# MPR121-Breakout-v13.net
KiCad netlist of a schematic drawn in EAGLE
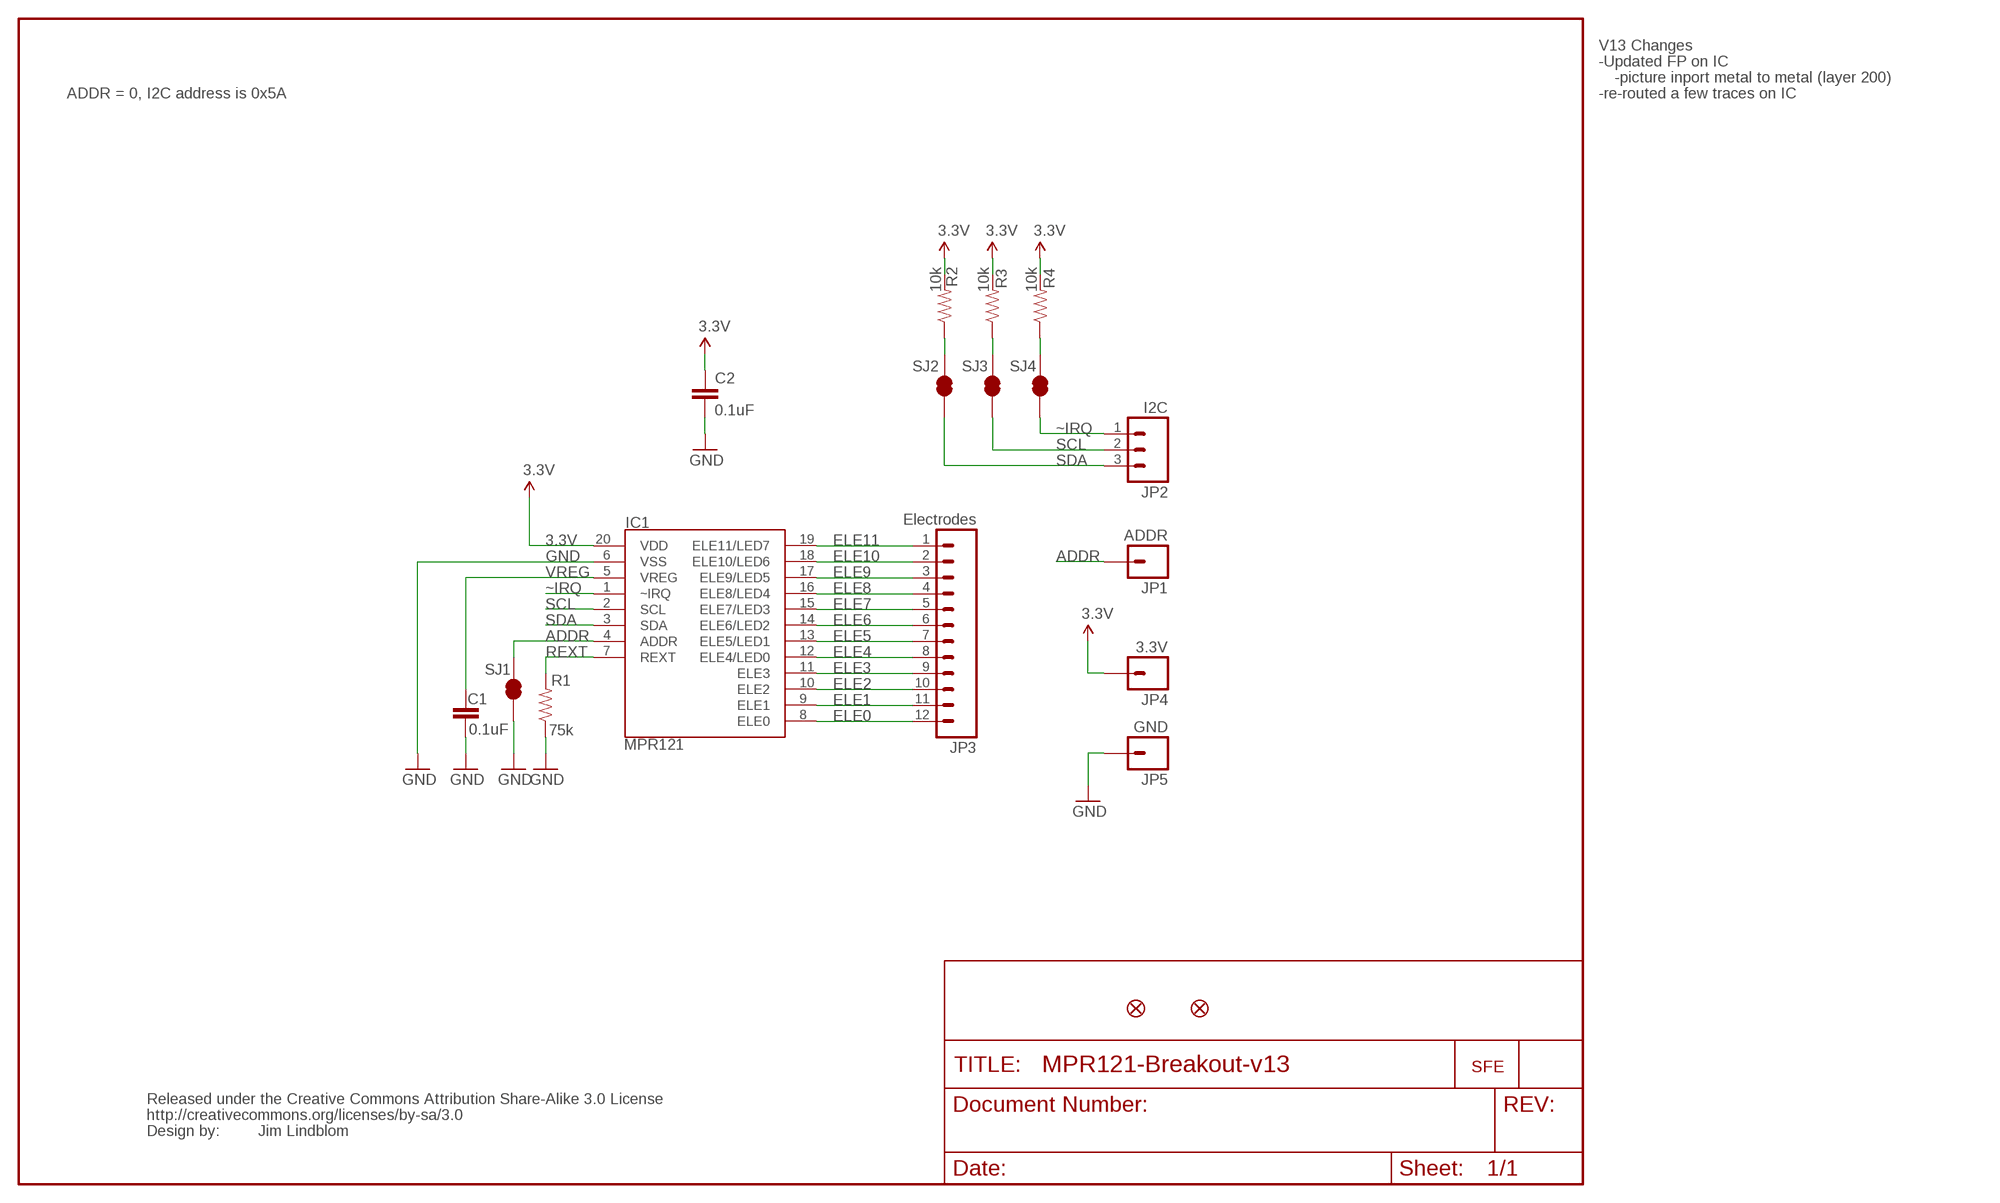
[diagram p0: schematic, sheet 1]

(export (version "E")
  (design (tool "Eeschema 10.0.6"))
  (components
    (comp (ref "C1")
      (value "0.1uF")
      (footprint "eagle-import:0603-CAP")
      (libsource (lib "eagle-import") (part "CAP0603-CAP"))
    )
    (comp (ref "C2")
      (value "0.1uF")
      (footprint "eagle-import:0603-CAP")
      (libsource (lib "eagle-import") (part "CAP0603-CAP"))
    )
    (comp (ref "IC1")
      (value "MPR121")
      (footprint "eagle-import:QFN-20-0.4MM-V2")
      (libsource (lib "eagle-import") (part "MPR121V2"))
    )
    (comp (ref "JP1")
      (value "ADDR")
      (footprint "eagle-import:1X01")
      (libsource (lib "eagle-import") (part "M01PTH"))
    )
    (comp (ref "JP2")
      (value "I2C")
      (footprint "eagle-import:1X03")
      (libsource (lib "eagle-import") (part "M03PTH"))
    )
    (comp (ref "JP3")
      (value "Electrodes")
      (footprint "eagle-import:1X12")
      (libsource (lib "eagle-import") (part "M12PTH"))
    )
    (comp (ref "JP4")
      (value "3.3V")
      (footprint "eagle-import:1X01")
      (libsource (lib "eagle-import") (part "M01PTH"))
    )
    (comp (ref "JP5")
      (value "GND")
      (footprint "eagle-import:1X01")
      (libsource (lib "eagle-import") (part "M01PTH"))
    )
    (comp (ref "JP7")
      (value "LOGO-SFENEW")
      (footprint "eagle-import:SFE-NEW-WEBLOGO")
      (libsource (lib "eagle-import") (part "LOGO-SFENEW"))
    )
    (comp (ref "JP8")
      (value "FIDUCIAL1X2")
      (footprint "eagle-import:FIDUCIAL-1X2")
      (libsource (lib "eagle-import") (part "FIDUCIAL1X2"))
    )
    (comp (ref "JP9")
      (value "FIDUCIAL1X2")
      (footprint "eagle-import:FIDUCIAL-1X2")
      (libsource (lib "eagle-import") (part "FIDUCIAL1X2"))
    )
    (comp (ref "R1")
      (value "75k")
      (footprint "eagle-import:0603-RES")
      (libsource (lib "eagle-import") (part "RESISTOR0603-RES"))
    )
    (comp (ref "R2")
      (value "10k")
      (footprint "eagle-import:0603-RES")
      (libsource (lib "eagle-import") (part "RESISTOR0603-RES"))
    )
    (comp (ref "R3")
      (value "10k")
      (footprint "eagle-import:0603-RES")
      (libsource (lib "eagle-import") (part "RESISTOR0603-RES"))
    )
    (comp (ref "R4")
      (value "10k")
      (footprint "eagle-import:0603-RES")
      (libsource (lib "eagle-import") (part "RESISTOR0603-RES"))
    )
    (comp (ref "SJ1")
      (value "SOLDERJUMPERTRACE")
      (footprint "eagle-import:SJ_2S-TRACE")
      (libsource (lib "eagle-import") (part "SOLDERJUMPERTRACE"))
    )
    (comp (ref "SJ2")
      (value "SOLDERJUMPERTRACE")
      (footprint "eagle-import:SJ_2S-TRACE")
      (libsource (lib "eagle-import") (part "SOLDERJUMPERTRACE"))
    )
    (comp (ref "SJ3")
      (value "SOLDERJUMPERTRACE")
      (footprint "eagle-import:SJ_2S-TRACE")
      (libsource (lib "eagle-import") (part "SOLDERJUMPERTRACE"))
    )
    (comp (ref "SJ4")
      (value "SOLDERJUMPERTRACE")
      (footprint "eagle-import:SJ_2S-TRACE")
      (libsource (lib "eagle-import") (part "SOLDERJUMPERTRACE"))
    )
    (comp (ref "U$1")
      (value "CREATIVE_COMMONS")
      (footprint "eagle-import:CREATIVE_COMMONS")
      (libsource (lib "eagle-import") (part "CREATIVE_COMMONS"))
    )
  )
  (nets
    (net (code "1") (name "/ADDR") (class "Default")
      (node (ref "IC1") (pin "4") (pinfunction "ADDR_4") (pintype "bidirectional"))
      (node (ref "JP1") (pin "1") (pinfunction "1_1") (pintype "passive"))
      (node (ref "SJ1") (pin "2") (pinfunction "2_2") (pintype "passive"))
    )
    (net (code "2") (name "/ELE0") (class "Default")
      (node (ref "IC1") (pin "8") (pinfunction "ELE0_8") (pintype "bidirectional"))
      (node (ref "JP3") (pin "12") (pinfunction "12_12") (pintype "passive"))
    )
    (net (code "3") (name "/ELE1") (class "Default")
      (node (ref "IC1") (pin "9") (pinfunction "ELE1_9") (pintype "bidirectional"))
      (node (ref "JP3") (pin "11") (pinfunction "11_11") (pintype "passive"))
    )
    (net (code "4") (name "/ELE2") (class "Default")
      (node (ref "IC1") (pin "10") (pinfunction "ELE2_10") (pintype "bidirectional"))
      (node (ref "JP3") (pin "10") (pinfunction "10_10") (pintype "passive"))
    )
    (net (code "5") (name "/ELE3") (class "Default")
      (node (ref "IC1") (pin "11") (pinfunction "ELE3_11") (pintype "bidirectional"))
      (node (ref "JP3") (pin "9") (pinfunction "9_9") (pintype "passive"))
    )
    (net (code "6") (name "/ELE4") (class "Default")
      (node (ref "IC1") (pin "12") (pinfunction "ELE4/LED0_12") (pintype "bidirectional"))
      (node (ref "JP3") (pin "8") (pinfunction "8_8") (pintype "passive"))
    )
    (net (code "7") (name "/ELE5") (class "Default")
      (node (ref "IC1") (pin "13") (pinfunction "ELE5/LED1_13") (pintype "bidirectional"))
      (node (ref "JP3") (pin "7") (pinfunction "7_7") (pintype "passive"))
    )
    (net (code "8") (name "/ELE6") (class "Default")
      (node (ref "IC1") (pin "14") (pinfunction "ELE6/LED2_14") (pintype "bidirectional"))
      (node (ref "JP3") (pin "6") (pinfunction "6_6") (pintype "passive"))
    )
    (net (code "9") (name "/ELE7") (class "Default")
      (node (ref "IC1") (pin "15") (pinfunction "ELE7/LED3_15") (pintype "bidirectional"))
      (node (ref "JP3") (pin "5") (pinfunction "5_5") (pintype "passive"))
    )
    (net (code "10") (name "/ELE8") (class "Default")
      (node (ref "IC1") (pin "16") (pinfunction "ELE8/LED4_16") (pintype "bidirectional"))
      (node (ref "JP3") (pin "4") (pinfunction "4_4") (pintype "passive"))
    )
    (net (code "11") (name "/ELE9") (class "Default")
      (node (ref "IC1") (pin "17") (pinfunction "ELE9/LED5_17") (pintype "bidirectional"))
      (node (ref "JP3") (pin "3") (pinfunction "3_3") (pintype "passive"))
    )
    (net (code "12") (name "/ELE10") (class "Default")
      (node (ref "IC1") (pin "18") (pinfunction "ELE10/LED6_18") (pintype "bidirectional"))
      (node (ref "JP3") (pin "2") (pinfunction "2_2") (pintype "passive"))
    )
    (net (code "13") (name "/ELE11") (class "Default")
      (node (ref "IC1") (pin "19") (pinfunction "ELE11/LED7_19") (pintype "bidirectional"))
      (node (ref "JP3") (pin "1") (pinfunction "1_1") (pintype "passive"))
    )
    (net (code "14") (name "/REXT") (class "Default")
      (node (ref "IC1") (pin "7") (pinfunction "REXT_7") (pintype "bidirectional"))
      (node (ref "R1") (pin "2") (pinfunction "2_2") (pintype "passive"))
    )
    (net (code "15") (name "/SCL") (class "Default")
      (node (ref "IC1") (pin "2") (pinfunction "SCL_2") (pintype "bidirectional"))
      (node (ref "JP2") (pin "2") (pinfunction "2_2") (pintype "passive"))
      (node (ref "SJ3") (pin "1") (pinfunction "1_1") (pintype "passive"))
    )
    (net (code "16") (name "/SDA") (class "Default")
      (node (ref "IC1") (pin "3") (pinfunction "SDA_3") (pintype "bidirectional"))
      (node (ref "JP2") (pin "3") (pinfunction "3_3") (pintype "passive"))
      (node (ref "SJ2") (pin "1") (pinfunction "1_1") (pintype "passive"))
    )
    (net (code "17") (name "/VREG") (class "Default")
      (node (ref "C1") (pin "1") (pinfunction "1_1") (pintype "passive"))
      (node (ref "IC1") (pin "5") (pinfunction "VREG_5") (pintype "bidirectional"))
    )
    (net (code "18") (name "/~{IRQ}") (class "Default")
      (node (ref "IC1") (pin "1") (pinfunction "~{IRQ}_1") (pintype "bidirectional"))
      (node (ref "JP2") (pin "1") (pinfunction "1_1") (pintype "passive"))
      (node (ref "SJ4") (pin "1") (pinfunction "1_1") (pintype "passive"))
    )
    (net (code "19") (name "3.3V") (class "Default")
      (node (ref "C2") (pin "1") (pinfunction "1_1") (pintype "passive"))
      (node (ref "IC1") (pin "20") (pinfunction "VDD_20") (pintype "bidirectional"))
      (node (ref "JP4") (pin "1") (pinfunction "1_1") (pintype "passive"))
      (node (ref "R2") (pin "2") (pinfunction "2_2") (pintype "passive"))
      (node (ref "R3") (pin "2") (pinfunction "2_2") (pintype "passive"))
      (node (ref "R4") (pin "2") (pinfunction "2_2") (pintype "passive"))
    )
    (net (code "20") (name "GND") (class "Default")
      (node (ref "C1") (pin "2") (pinfunction "2_2") (pintype "passive"))
      (node (ref "C2") (pin "2") (pinfunction "2_2") (pintype "passive"))
      (node (ref "IC1") (pin "6") (pinfunction "VSS_6") (pintype "bidirectional"))
      (node (ref "JP5") (pin "1") (pinfunction "1_1") (pintype "passive"))
      (node (ref "R1") (pin "1") (pinfunction "1_1") (pintype "passive"))
      (node (ref "SJ1") (pin "1") (pinfunction "1_1") (pintype "passive"))
    )
    (net (code "21") (name "Net-(R2-Pad1)") (class "Default")
      (node (ref "R2") (pin "1") (pinfunction "1_1") (pintype "passive"))
      (node (ref "SJ2") (pin "2") (pinfunction "2_2") (pintype "passive"))
    )
    (net (code "22") (name "Net-(R3-Pad1)") (class "Default")
      (node (ref "R3") (pin "1") (pinfunction "1_1") (pintype "passive"))
      (node (ref "SJ3") (pin "2") (pinfunction "2_2") (pintype "passive"))
    )
    (net (code "23") (name "Net-(R4-Pad1)") (class "Default")
      (node (ref "R4") (pin "1") (pinfunction "1_1") (pintype "passive"))
      (node (ref "SJ4") (pin "2") (pinfunction "2_2") (pintype "passive"))
    )
  )
)
